# ecd.net
KiCad netlist of a schematic drawn in EAGLE
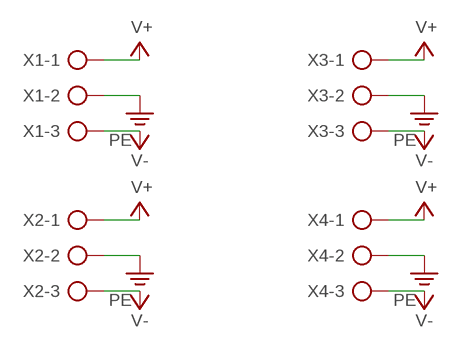
[diagram p0: schematic, sheet 1]

(export (version "E")
  (design (tool "Eeschema 10.0.6"))
  (components
    (comp (ref "X1")
      (value "AK500/3")
      (footprint "eagle-import:AK500_3")
      (libsource (lib "eagle-import") (part "AK500/3"))
    )
    (comp (ref "X2")
      (value "AK500/3")
      (footprint "eagle-import:AK500_3")
      (libsource (lib "eagle-import") (part "AK500/3"))
    )
    (comp (ref "X3")
      (value "AK500/3")
      (footprint "eagle-import:AK500_3")
      (libsource (lib "eagle-import") (part "AK500/3"))
    )
    (comp (ref "X4")
      (value "AK500/3")
      (footprint "eagle-import:AK500_3")
      (libsource (lib "eagle-import") (part "AK500/3"))
    )
  )
  (nets
    (net (code "1") (name "PE") (class "Default")
      (node (ref "X1") (pin "2") (pinfunction "KL_2") (pintype "passive"))
      (node (ref "X2") (pin "2") (pinfunction "KL_2") (pintype "passive"))
      (node (ref "X3") (pin "2") (pinfunction "KL_2") (pintype "passive"))
      (node (ref "X4") (pin "2") (pinfunction "KL_2") (pintype "passive"))
    )
    (net (code "2") (name "V+") (class "Default")
      (node (ref "X1") (pin "1") (pinfunction "KL_1") (pintype "passive"))
      (node (ref "X2") (pin "1") (pinfunction "KL_1") (pintype "passive"))
      (node (ref "X3") (pin "1") (pinfunction "KL_1") (pintype "passive"))
      (node (ref "X4") (pin "1") (pinfunction "KL_1") (pintype "passive"))
    )
    (net (code "3") (name "V-") (class "Default")
      (node (ref "X1") (pin "3") (pinfunction "KL_3") (pintype "passive"))
      (node (ref "X2") (pin "3") (pinfunction "KL_3") (pintype "passive"))
      (node (ref "X3") (pin "3") (pinfunction "KL_3") (pintype "passive"))
      (node (ref "X4") (pin "3") (pinfunction "KL_3") (pintype "passive"))
    )
  )
)
